# Main.net
KiCad netlist of a schematic drawn in Altium Designer
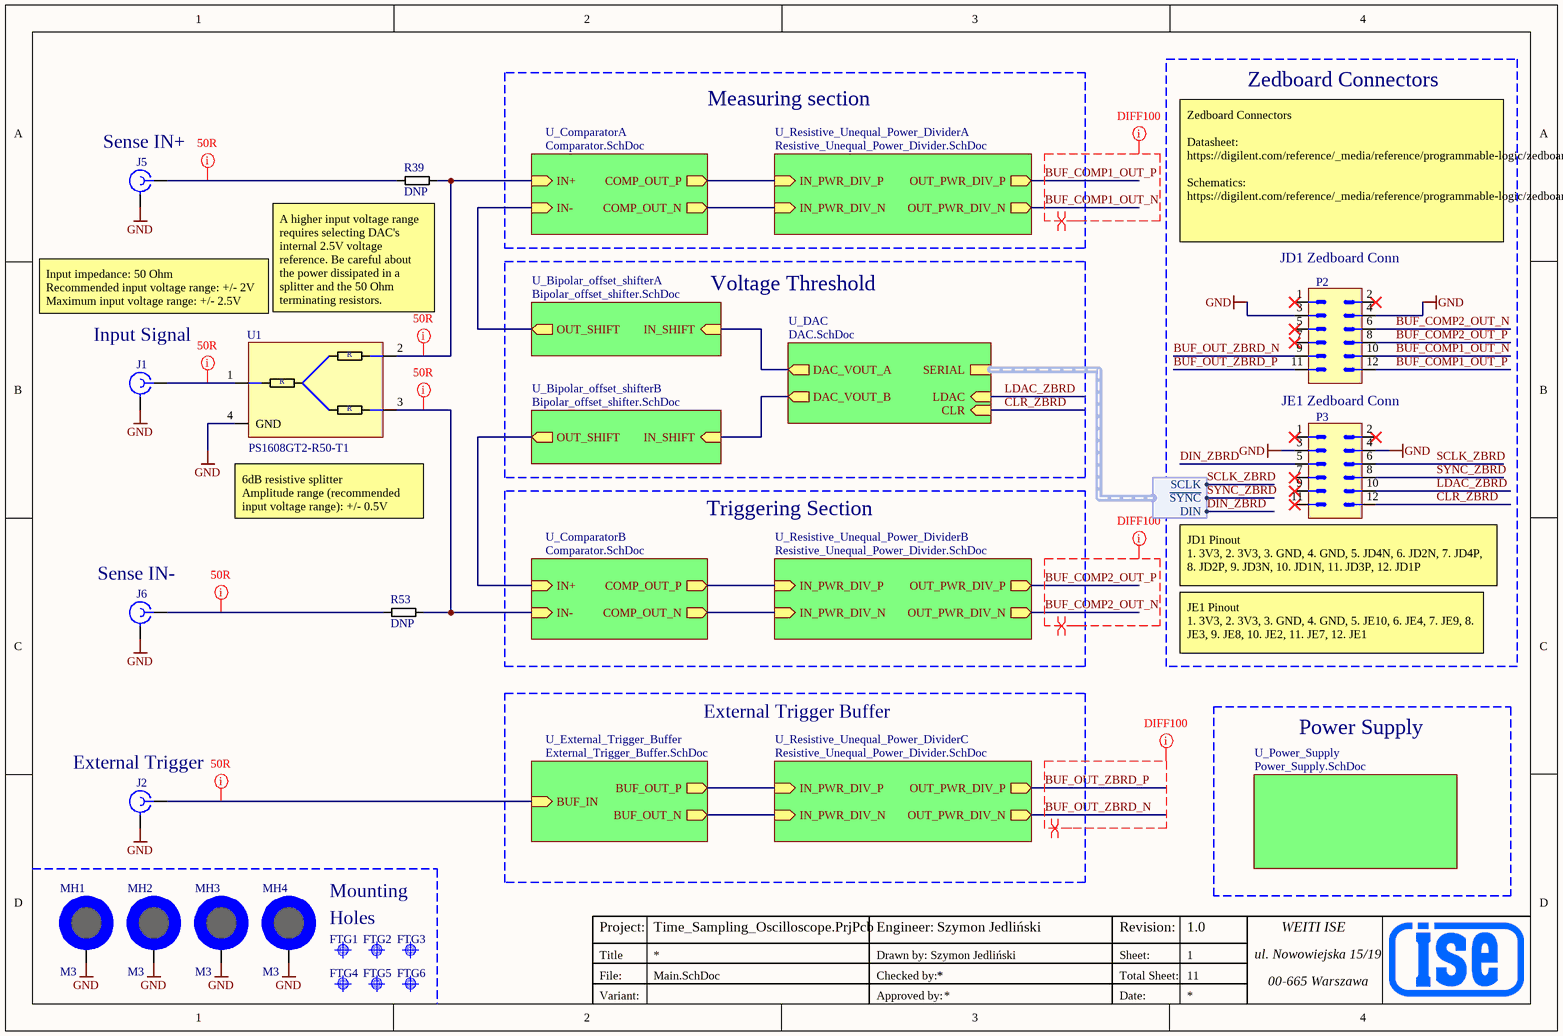
[diagram p0: Main.SchDoc]

(export (version "E")
  (design (tool "Eeschema 10.0.6"))
  (components
    (comp (ref "FTG1")
      (value "Fiducial")
      (footprint "FIDUCIAL_TOP_S100-200")
      (description "Square Fiducial Target, Top Layer, 1.0mm, Top Solder 2.0mm, Keepout =2.0mm")
      (libsource (lib "Mechanical_and_PCB_Features") (part "Fiducial Target"))
    )
    (comp (ref "FTG2")
      (value "Fiducial")
      (footprint "FIDUCIAL_TOP_S100-200")
      (description "Square Fiducial Target, Top Layer, 1.0mm, Top Solder 2.0mm, Keepout =2.0mm")
      (libsource (lib "Mechanical_and_PCB_Features") (part "Fiducial Target"))
    )
    (comp (ref "FTG3")
      (value "Fiducial")
      (footprint "FIDUCIAL_TOP_S100-200")
      (description "Square Fiducial Target, Top Layer, 1.0mm, Top Solder 2.0mm, Keepout =2.0mm")
      (libsource (lib "Mechanical_and_PCB_Features") (part "Fiducial Target"))
    )
    (comp (ref "FTG4")
      (value "Fiducial")
      (footprint "FIDUCIAL_BOT_S100-200")
      (description "Square Fiducial Target, Bot Layer, 1.0mm, Bot Solder 2.0mm, Keepout =2.0mm")
      (libsource (lib "Mechanical_and_PCB_Features") (part "Fiducial Target"))
    )
    (comp (ref "FTG5")
      (value "Fiducial")
      (footprint "FIDUCIAL_BOT_S100-200")
      (description "Square Fiducial Target, Bot Layer, 1.0mm, Bot Solder 2.0mm, Keepout =2.0mm")
      (libsource (lib "Mechanical_and_PCB_Features") (part "Fiducial Target"))
    )
    (comp (ref "FTG6")
      (value "Fiducial")
      (footprint "FIDUCIAL_BOT_S100-200")
      (description "Square Fiducial Target, Bot Layer, 1.0mm, Bot Solder 2.0mm, Keepout =2.0mm")
      (libsource (lib "Mechanical_and_PCB_Features") (part "Fiducial Target"))
    )
    (comp (ref "J1")
      (value "CONSMA020.062-G")
      (footprint "CONSMA020.062-G")
      (description "Coaxial Connectors SMA, Edge Mount, Female Receptacle, 0.062\" PCB Mount, Gold")
      (libsource (lib "Connectors") (part "Coax_1Female_1Shield"))
    )
    (comp (ref "J2")
      (value "CONSMA020.062-G")
      (footprint "CONSMA020.062-G")
      (description "Coaxial Connectors SMA, Edge Mount, Female Receptacle, 0.062\" PCB Mount, Gold")
      (libsource (lib "Connectors") (part "Coax_1Female_1Shield"))
    )
    (comp (ref "J5")
      (value "CONSMA020.062-G")
      (footprint "CONSMA020.062-G")
      (description "Coaxial Connectors SMA, Edge Mount, Female Receptacle, 0.062\" PCB Mount, Gold")
      (libsource (lib "Connectors") (part "Coax_1Female_1Shield"))
    )
    (comp (ref "J6")
      (value "CONSMA020.062-G")
      (footprint "CONSMA020.062-G")
      (description "Coaxial Connectors SMA, Edge Mount, Female Receptacle, 0.062\" PCB Mount, Gold")
      (libsource (lib "Connectors") (part "Coax_1Female_1Shield"))
    )
    (comp (ref "MH1")
      (value "M3")
      (footprint "MH-M3_COPPER")
      (description "Mounting hole, M3, exposed pad")
      (libsource (lib "Mechanical_and_PCB_Features") (part "MH"))
    )
    (comp (ref "MH2")
      (value "M3")
      (footprint "MH-M3_COPPER")
      (description "Mounting hole, M3, exposed pad")
      (libsource (lib "Mechanical_and_PCB_Features") (part "MH"))
    )
    (comp (ref "MH3")
      (value "M3")
      (footprint "MH-M3_COPPER")
      (description "Mounting hole, M3, exposed pad")
      (libsource (lib "Mechanical_and_PCB_Features") (part "MH"))
    )
    (comp (ref "MH4")
      (value "M3")
      (footprint "MH-M3_COPPER")
      (description "Mounting hole, M3, exposed pad")
      (libsource (lib "Mechanical_and_PCB_Features") (part "MH"))
    )
    (comp (ref "P2")
      (value "WURTH_610112249121")
      (footprint "WURTH_610112249121")
      (description "WR-PHD SMT Angled Dual Pin Header, 2.54mm, 2x6")
      (libsource (lib "Connectors") (part "Header 6x2"))
    )
    (comp (ref "P3")
      (value "WURTH_610112249121")
      (footprint "WURTH_610112249121")
      (description "WR-PHD SMT Angled Dual Pin Header, 2.54mm, 2x6")
      (libsource (lib "Connectors") (part "Header 6x2"))
    )
    (comp (ref "R39")
      (value "DNP")
      (footprint "RESC0402X40N")
      (description "General Purpose Thick Film Chip Resistor")
      (fields (field (name "VOLTAGE") "50V"))
      (libsource (lib "Resistors") (part "Resistor - Generic"))
    )
    (comp (ref "R53")
      (value "DNP")
      (footprint "RESC0402X40N")
      (description "General Purpose Thick Film Chip Resistor")
      (fields (field (name "VOLTAGE") "50V"))
      (libsource (lib "Resistors") (part "Resistor - Generic"))
    )
    (comp (ref "U1")
      (value "PS1608GT2-R50-T1")
      (footprint "PS1608GT2R50T1")
      (description "Signal Conditioning 50 ohm 2 terminal Power Splitter")
      (libsource (lib "Resistors") (part "PSXXXXGT2-R50"))
    )
  )
  (nets
    (net (code "2") (name "/BUF_COMP1_OUT_N") (class "Default")
      (node (ref "P2") (pin "10") (pinfunction "10_10") (pintype "passive"))
    )
    (net (code "3") (name "/BUF_COMP1_OUT_P") (class "Default")
      (node (ref "P2") (pin "12") (pinfunction "12_12") (pintype "passive"))
    )
    (net (code "4") (name "/BUF_COMP2_OUT_N") (class "Default")
      (node (ref "P2") (pin "6") (pinfunction "6_6") (pintype "passive"))
    )
    (net (code "5") (name "/BUF_COMP2_OUT_P") (class "Default")
      (node (ref "P2") (pin "8") (pinfunction "8_8") (pintype "passive"))
    )
    (net (code "6") (name "/BUF_IN") (class "Default")
      (node (ref "J2") (pin "1") (pinfunction "1_1") (pintype "passive"))
    )
    (net (code "9") (name "/BUF_OUT_ZBRD_N") (class "Default")
      (node (ref "P2") (pin "9") (pinfunction "9_9") (pintype "passive"))
    )
    (net (code "10") (name "/BUF_OUT_ZBRD_P") (class "Default")
      (node (ref "P2") (pin "11") (pinfunction "11_11") (pintype "passive"))
    )
    (net (code "11") (name "/CLR_ZBRD") (class "Default")
      (node (ref "P3") (pin "12") (pinfunction "12_12") (pintype "passive"))
    )
    (net (code "18") (name "/DIN_ZBRD") (class "Default")
      (node (ref "P3") (pin "5") (pinfunction "5_5") (pintype "passive"))
    )
    (net (code "19") (name "/IN+") (class "Default")
      (node (ref "R39") (pin "1") (pinfunction "1_1") (pintype "passive"))
      (node (ref "U1") (pin "2") (pinfunction "2_2") (pintype "passive"))
    )
    (net (code "20") (name "/IN-") (class "Default")
      (node (ref "R53") (pin "2") (pinfunction "2_2") (pintype "passive"))
      (node (ref "U1") (pin "3") (pinfunction "3_3") (pintype "passive"))
    )
    (net (code "21") (name "/LDAC_ZBRD") (class "Default")
      (node (ref "P3") (pin "10") (pinfunction "10_10") (pintype "passive"))
    )
    (net (code "24") (name "/SCLK_ZBRD") (class "Default")
      (node (ref "P3") (pin "6") (pinfunction "6_6") (pintype "passive"))
    )
    (net (code "25") (name "/SYNC_ZBRD") (class "Default")
      (node (ref "P3") (pin "8") (pinfunction "8_8") (pintype "passive"))
    )
    (net (code "27") (name "GND") (class "Default")
      (node (ref "J1") (pin "2") (pinfunction "2_2") (pintype "passive"))
      (node (ref "J2") (pin "2") (pinfunction "2_2") (pintype "passive"))
      (node (ref "J5") (pin "2") (pinfunction "2_2") (pintype "passive"))
      (node (ref "J6") (pin "2") (pinfunction "2_2") (pintype "passive"))
      (node (ref "MH1") (pin "MH") (pinfunction "MH_MH") (pintype "passive"))
      (node (ref "MH2") (pin "MH") (pinfunction "MH_MH") (pintype "passive"))
      (node (ref "MH3") (pin "MH") (pinfunction "MH_MH") (pintype "passive"))
      (node (ref "MH4") (pin "MH") (pinfunction "MH_MH") (pintype "passive"))
      (node (ref "P2") (pin "3") (pinfunction "3_3") (pintype "passive"))
      (node (ref "P2") (pin "4") (pinfunction "4_4") (pintype "passive"))
      (node (ref "P3") (pin "3") (pinfunction "3_3") (pintype "passive"))
      (node (ref "P3") (pin "4") (pinfunction "4_4") (pintype "passive"))
      (node (ref "U1") (pin "4") (pinfunction "GND_4") (pintype "passive"))
    )
    (net (code "28") (name "Net-(J1-Pad1)") (class "Default")
      (node (ref "J1") (pin "1") (pinfunction "1_1") (pintype "passive"))
      (node (ref "U1") (pin "1") (pinfunction "1_1") (pintype "passive"))
    )
    (net (code "29") (name "Net-(J5-Pad1)") (class "Default")
      (node (ref "J5") (pin "1") (pinfunction "1_1") (pintype "passive"))
      (node (ref "R39") (pin "2") (pinfunction "2_2") (pintype "passive"))
    )
    (net (code "30") (name "Net-(J6-Pad1)") (class "Default")
      (node (ref "J6") (pin "1") (pinfunction "1_1") (pintype "passive"))
      (node (ref "R53") (pin "1") (pinfunction "1_1") (pintype "passive"))
    )
    (net (code "31") (name "unconnected-(P2-Pad1)") (class "Default")
      (node (ref "P2") (pin "1") (pinfunction "1_1") (pintype "passive+no_connect"))
    )
    (net (code "32") (name "unconnected-(P2-Pad2)") (class "Default")
      (node (ref "P2") (pin "2") (pinfunction "2_2") (pintype "passive+no_connect"))
    )
    (net (code "33") (name "unconnected-(P2-Pad5)") (class "Default")
      (node (ref "P2") (pin "5") (pinfunction "5_5") (pintype "passive+no_connect"))
    )
    (net (code "34") (name "unconnected-(P2-Pad7)") (class "Default")
      (node (ref "P2") (pin "7") (pinfunction "7_7") (pintype "passive+no_connect"))
    )
    (net (code "35") (name "unconnected-(P3-Pad1)") (class "Default")
      (node (ref "P3") (pin "1") (pinfunction "1_1") (pintype "passive+no_connect"))
    )
    (net (code "36") (name "unconnected-(P3-Pad2)") (class "Default")
      (node (ref "P3") (pin "2") (pinfunction "2_2") (pintype "passive+no_connect"))
    )
    (net (code "37") (name "unconnected-(P3-Pad7)") (class "Default")
      (node (ref "P3") (pin "7") (pinfunction "7_7") (pintype "passive+no_connect"))
    )
    (net (code "38") (name "unconnected-(P3-Pad9)") (class "Default")
      (node (ref "P3") (pin "9") (pinfunction "9_9") (pintype "passive+no_connect"))
    )
    (net (code "39") (name "unconnected-(P3-Pad11)") (class "Default")
      (node (ref "P3") (pin "11") (pinfunction "11_11") (pintype "passive+no_connect"))
    )
  )
)
